# w5500-004.net
KiCad netlist of a schematic drawn in EAGLE
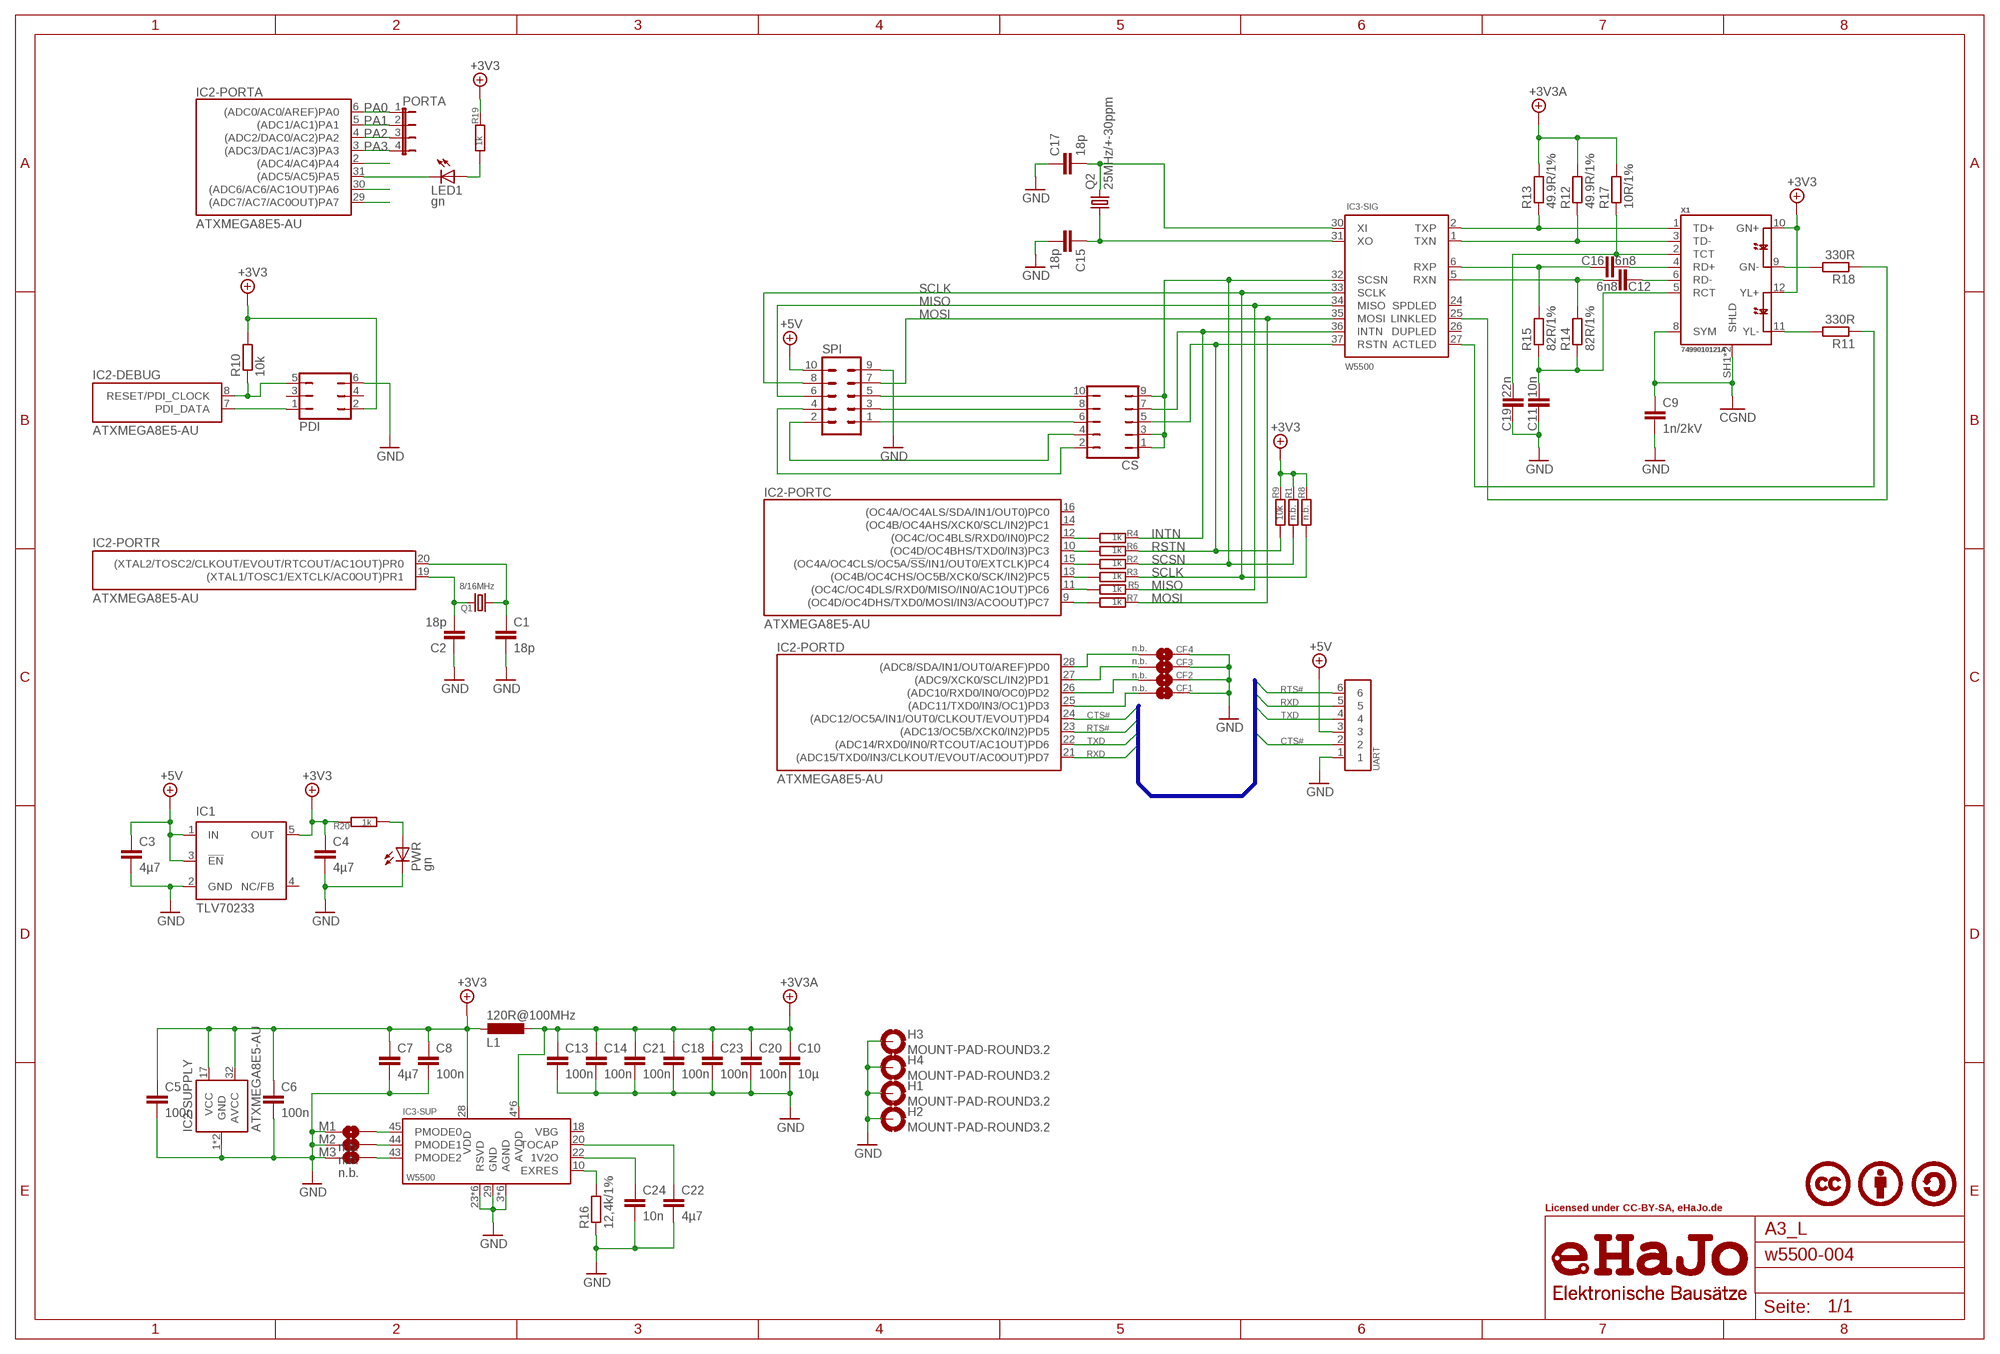
[diagram p0: schematic, sheet 1]

(export (version "E")
  (design (tool "Eeschema 10.0.6"))
  (components
    (comp (ref "C1")
      (value "18p")
      (footprint "eagle-import:C0603")
      (libsource (lib "eagle-import") (part "CC0603"))
    )
    (comp (ref "C2")
      (value "18p")
      (footprint "eagle-import:C0603")
      (libsource (lib "eagle-import") (part "CC0603"))
    )
    (comp (ref "C3")
      (value "4µ7")
      (footprint "eagle-import:C0805")
      (libsource (lib "eagle-import") (part "CC0805"))
    )
    (comp (ref "C4")
      (value "4µ7")
      (footprint "eagle-import:C0805")
      (libsource (lib "eagle-import") (part "CC0805"))
    )
    (comp (ref "C5")
      (value "100n")
      (footprint "eagle-import:C0603")
      (libsource (lib "eagle-import") (part "CC0603"))
    )
    (comp (ref "C6")
      (value "100n")
      (footprint "eagle-import:C0603")
      (libsource (lib "eagle-import") (part "CC0603"))
    )
    (comp (ref "C7")
      (value "4µ7")
      (footprint "eagle-import:C0805")
      (libsource (lib "eagle-import") (part "CC0805"))
    )
    (comp (ref "C8")
      (value "100n")
      (footprint "eagle-import:C0603")
      (libsource (lib "eagle-import") (part "CC0603"))
    )
    (comp (ref "C9")
      (value "1n/2kV")
      (footprint "eagle-import:C0805")
      (libsource (lib "eagle-import") (part "CC0805"))
    )
    (comp (ref "C10")
      (value "10µ")
      (footprint "eagle-import:C1206")
      (libsource (lib "eagle-import") (part "CC1206"))
    )
    (comp (ref "C11")
      (value "10n")
      (footprint "eagle-import:C0603")
      (libsource (lib "eagle-import") (part "CC0603"))
    )
    (comp (ref "C12")
      (value "6n8")
      (footprint "eagle-import:C0603")
      (libsource (lib "eagle-import") (part "CC0603"))
    )
    (comp (ref "C13")
      (value "100n")
      (footprint "eagle-import:C0603")
      (libsource (lib "eagle-import") (part "CC0603"))
    )
    (comp (ref "C14")
      (value "100n")
      (footprint "eagle-import:C0603")
      (libsource (lib "eagle-import") (part "CC0603"))
    )
    (comp (ref "C15")
      (value "18p")
      (footprint "eagle-import:C0603")
      (libsource (lib "eagle-import") (part "CC0603"))
    )
    (comp (ref "C16")
      (value "6n8")
      (footprint "eagle-import:C0603")
      (libsource (lib "eagle-import") (part "CC0603"))
    )
    (comp (ref "C17")
      (value "18p")
      (footprint "eagle-import:C0603")
      (libsource (lib "eagle-import") (part "CC0603"))
    )
    (comp (ref "C18")
      (value "100n")
      (footprint "eagle-import:C0603")
      (libsource (lib "eagle-import") (part "CC0603"))
    )
    (comp (ref "C19")
      (value "22n")
      (footprint "eagle-import:C0603")
      (libsource (lib "eagle-import") (part "CC0603"))
    )
    (comp (ref "C20")
      (value "100n")
      (footprint "eagle-import:C0603")
      (libsource (lib "eagle-import") (part "CC0603"))
    )
    (comp (ref "C21")
      (value "100n")
      (footprint "eagle-import:C0603")
      (libsource (lib "eagle-import") (part "CC0603"))
    )
    (comp (ref "C22")
      (value "4µ7")
      (footprint "eagle-import:C0805")
      (libsource (lib "eagle-import") (part "CC0805"))
    )
    (comp (ref "C23")
      (value "100n")
      (footprint "eagle-import:C0603")
      (libsource (lib "eagle-import") (part "CC0603"))
    )
    (comp (ref "C24")
      (value "10n")
      (footprint "eagle-import:C0603")
      (libsource (lib "eagle-import") (part "CC0603"))
    )
    (comp (ref "CF1")
      (value "n.b.")
      (footprint "eagle-import:SJS")
      (libsource (lib "eagle-import") (part "SJS"))
    )
    (comp (ref "CF2")
      (value "n.b.")
      (footprint "eagle-import:SJS")
      (libsource (lib "eagle-import") (part "SJS"))
    )
    (comp (ref "CF3")
      (value "n.b.")
      (footprint "eagle-import:SJS")
      (libsource (lib "eagle-import") (part "SJS"))
    )
    (comp (ref "CF4")
      (value "n.b.")
      (footprint "eagle-import:SJS")
      (libsource (lib "eagle-import") (part "SJS"))
    )
    (comp (ref "CS")
      (value "JP5Q")
      (footprint "eagle-import:JP5Q")
      (libsource (lib "eagle-import") (part "JP5Q"))
    )
    (comp (ref "H1")
      (value "MOUNT-PAD-ROUND3.2")
      (footprint "eagle-import:3,2-PAD")
      (libsource (lib "eagle-import") (part "MOUNT-PAD-ROUND3.2"))
    )
    (comp (ref "H2")
      (value "MOUNT-PAD-ROUND3.2")
      (footprint "eagle-import:3,2-PAD")
      (libsource (lib "eagle-import") (part "MOUNT-PAD-ROUND3.2"))
    )
    (comp (ref "H3")
      (value "MOUNT-PAD-ROUND3.2")
      (footprint "eagle-import:3,2-PAD")
      (libsource (lib "eagle-import") (part "MOUNT-PAD-ROUND3.2"))
    )
    (comp (ref "H4")
      (value "MOUNT-PAD-ROUND3.2")
      (footprint "eagle-import:3,2-PAD")
      (libsource (lib "eagle-import") (part "MOUNT-PAD-ROUND3.2"))
    )
    (comp (ref "IC1")
      (value "TLV70233")
      (footprint "eagle-import:SOT23-DBV")
      (libsource (lib "eagle-import") (part "TPS77001"))
    )
    (comp (ref "IC2")
      (value "ATXMEGA8E5-AU")
      (footprint "eagle-import:TQFP32-08")
      (libsource (lib "eagle-import") (part "ATXMEGAE5-AU"))
    )
    (comp (ref "IC3")
      (value "W5500")
      (footprint "eagle-import:LQFP48")
      (libsource (lib "eagle-import") (part "W5500"))
    )
    (comp (ref "L1")
      (value "120R@100MHz")
      (footprint "eagle-import:R0805")
      (libsource (lib "eagle-import") (part "L0805"))
    )
    (comp (ref "LED1")
      (value "gn")
      (footprint "eagle-import:CHIP-LED0805")
      (libsource (lib "eagle-import") (part "LEDCHIP-LED0805"))
    )
    (comp (ref "M1")
      (value "n.b.")
      (footprint "eagle-import:SJS")
      (libsource (lib "eagle-import") (part "SJS"))
    )
    (comp (ref "M2")
      (value "n.b.")
      (footprint "eagle-import:SJS")
      (libsource (lib "eagle-import") (part "SJS"))
    )
    (comp (ref "M3")
      (value "n.b.")
      (footprint "eagle-import:SJS")
      (libsource (lib "eagle-import") (part "SJS"))
    )
    (comp (ref "PDI")
      (value "JP3Q")
      (footprint "eagle-import:JP3Q")
      (libsource (lib "eagle-import") (part "JP3Q"))
    )
    (comp (ref "PORTA")
      (value "JP4ESML")
      (footprint "eagle-import:4SML")
      (libsource (lib "eagle-import") (part "JP4ESML"))
    )
    (comp (ref "PWR")
      (value "gn")
      (footprint "eagle-import:CHIP-LED0805")
      (libsource (lib "eagle-import") (part "LEDCHIP-LED0805"))
    )
    (comp (ref "Q1")
      (value "8/16MHz")
      (footprint "eagle-import:HC49U70")
      (libsource (lib "eagle-import") (part "CRYSTALHC49U70"))
    )
    (comp (ref "Q2")
      (value "25MHz/+-30ppm")
      (footprint "eagle-import:HC49U70")
      (libsource (lib "eagle-import") (part "CRYSTALHC49U70"))
    )
    (comp (ref "R1")
      (value "n.b.")
      (footprint "eagle-import:R0603")
      (libsource (lib "eagle-import") (part "RR0603"))
    )
    (comp (ref "R2")
      (value "1k")
      (footprint "eagle-import:R0603")
      (libsource (lib "eagle-import") (part "RR0603"))
    )
    (comp (ref "R3")
      (value "1k")
      (footprint "eagle-import:R0603")
      (libsource (lib "eagle-import") (part "RR0603"))
    )
    (comp (ref "R4")
      (value "1k")
      (footprint "eagle-import:R0603")
      (libsource (lib "eagle-import") (part "RR0603"))
    )
    (comp (ref "R5")
      (value "1k")
      (footprint "eagle-import:R0603")
      (libsource (lib "eagle-import") (part "RR0603"))
    )
    (comp (ref "R6")
      (value "1k")
      (footprint "eagle-import:R0603")
      (libsource (lib "eagle-import") (part "RR0603"))
    )
    (comp (ref "R7")
      (value "1k")
      (footprint "eagle-import:R0603")
      (libsource (lib "eagle-import") (part "RR0603"))
    )
    (comp (ref "R8")
      (value "n.b.")
      (footprint "eagle-import:R0603")
      (libsource (lib "eagle-import") (part "RR0603"))
    )
    (comp (ref "R9")
      (value "10k")
      (footprint "eagle-import:R0603")
      (libsource (lib "eagle-import") (part "RR0603"))
    )
    (comp (ref "R10")
      (value "10k")
      (footprint "eagle-import:R0603")
      (libsource (lib "eagle-import") (part "RR0603"))
    )
    (comp (ref "R11")
      (value "330R")
      (footprint "eagle-import:R0603")
      (libsource (lib "eagle-import") (part "RR0603"))
    )
    (comp (ref "R12")
      (value "49.9R/1%")
      (footprint "eagle-import:R0603")
      (libsource (lib "eagle-import") (part "RR0603"))
    )
    (comp (ref "R13")
      (value "49.9R/1%")
      (footprint "eagle-import:R0603")
      (libsource (lib "eagle-import") (part "RR0603"))
    )
    (comp (ref "R14")
      (value "82R/1%")
      (footprint "eagle-import:R0603")
      (libsource (lib "eagle-import") (part "RR0603"))
    )
    (comp (ref "R15")
      (value "82R/1%")
      (footprint "eagle-import:R0603")
      (libsource (lib "eagle-import") (part "RR0603"))
    )
    (comp (ref "R16")
      (value "12,4k/1%")
      (footprint "eagle-import:R0603")
      (libsource (lib "eagle-import") (part "RR0603"))
    )
    (comp (ref "R17")
      (value "10R/1%")
      (footprint "eagle-import:R0603")
      (libsource (lib "eagle-import") (part "RR0603"))
    )
    (comp (ref "R18")
      (value "330R")
      (footprint "eagle-import:R0603")
      (libsource (lib "eagle-import") (part "RR0603"))
    )
    (comp (ref "R19")
      (value "1k")
      (footprint "eagle-import:R0603")
      (libsource (lib "eagle-import") (part "RR0603"))
    )
    (comp (ref "R20")
      (value "1k")
      (footprint "eagle-import:R0603")
      (libsource (lib "eagle-import") (part "RR0603"))
    )
    (comp (ref "SPI")
      (value "ML10")
      (footprint "eagle-import:ML10")
      (libsource (lib "eagle-import") (part "ML10"))
    )
    (comp (ref "UART")
      (value "JP6E")
      (footprint "eagle-import:JP6E")
      (libsource (lib "eagle-import") (part "JP6E"))
    )
    (comp (ref "X1")
      (value "7499010121A")
      (footprint "eagle-import:121A")
      (libsource (lib "eagle-import") (part "7499010121"))
    )
  )
  (nets
    (net (code "1") (name "+3V3") (class "Default")
      (node (ref "C4") (pin "1") (pinfunction "1_1") (pintype "passive"))
      (node (ref "C5") (pin "1") (pinfunction "1_1") (pintype "passive"))
      (node (ref "C6") (pin "1") (pinfunction "1_1") (pintype "passive"))
      (node (ref "C7") (pin "1") (pinfunction "1_1") (pintype "passive"))
      (node (ref "C8") (pin "1") (pinfunction "1_1") (pintype "passive"))
      (node (ref "IC1") (pin "5") (pinfunction "OUT_5") (pintype "passive"))
      (node (ref "IC2") (pin "17") (pinfunction "VCC_17") (pintype "bidirectional"))
      (node (ref "IC2") (pin "32") (pinfunction "AVCC_32") (pintype "bidirectional"))
      (node (ref "IC3") (pin "28") (pinfunction "VDD_28") (pintype "power_in"))
      (node (ref "L1") (pin "2") (pinfunction "2_2") (pintype "passive"))
      (node (ref "PDI") (pin "2") (pinfunction "2_2") (pintype "passive"))
      (node (ref "R1") (pin "2") (pinfunction "2_2") (pintype "passive"))
      (node (ref "R10") (pin "2") (pinfunction "2_2") (pintype "passive"))
      (node (ref "R19") (pin "2") (pinfunction "2_2") (pintype "passive"))
      (node (ref "R20") (pin "2") (pinfunction "2_2") (pintype "passive"))
      (node (ref "R8") (pin "2") (pinfunction "2_2") (pintype "passive"))
      (node (ref "R9") (pin "2") (pinfunction "2_2") (pintype "passive"))
      (node (ref "X1") (pin "10") (pinfunction "GN+_10") (pintype "bidirectional"))
      (node (ref "X1") (pin "12") (pinfunction "YL+_12") (pintype "bidirectional"))
    )
    (net (code "2") (name "+3V3A") (class "Default")
      (node (ref "C10") (pin "1") (pinfunction "1_1") (pintype "passive"))
      (node (ref "C13") (pin "1") (pinfunction "1_1") (pintype "passive"))
      (node (ref "C14") (pin "1") (pinfunction "1_1") (pintype "passive"))
      (node (ref "C18") (pin "1") (pinfunction "1_1") (pintype "passive"))
      (node (ref "C20") (pin "1") (pinfunction "1_1") (pintype "passive"))
      (node (ref "C21") (pin "1") (pinfunction "1_1") (pintype "passive"))
      (node (ref "C23") (pin "1") (pinfunction "1_1") (pintype "passive"))
      (node (ref "IC3") (pin "11") (pinfunction "AVDD_11") (pintype "power_in"))
      (node (ref "IC3") (pin "15") (pinfunction "AVDD_15") (pintype "power_in"))
      (node (ref "IC3") (pin "17") (pinfunction "AVDD_17") (pintype "power_in"))
      (node (ref "IC3") (pin "21") (pinfunction "AVDD_21") (pintype "power_in"))
      (node (ref "IC3") (pin "4") (pinfunction "AVDD_4") (pintype "power_in"))
      (node (ref "IC3") (pin "8") (pinfunction "AVDD_8") (pintype "power_in"))
      (node (ref "L1") (pin "1") (pinfunction "1_1") (pintype "passive"))
      (node (ref "R12") (pin "2") (pinfunction "2_2") (pintype "passive"))
      (node (ref "R13") (pin "2") (pinfunction "2_2") (pintype "passive"))
      (node (ref "R17") (pin "2") (pinfunction "2_2") (pintype "passive"))
    )
    (net (code "3") (name "+5V") (class "Default")
      (node (ref "C3") (pin "1") (pinfunction "1_1") (pintype "passive"))
      (node (ref "IC1") (pin "1") (pinfunction "IN_1") (pintype "input"))
      (node (ref "IC1") (pin "3") (pinfunction "~{EN}_3") (pintype "input"))
      (node (ref "SPI") (pin "10") (pinfunction "10_10") (pintype "passive"))
      (node (ref "UART") (pin "3") (pinfunction "3_3") (pintype "bidirectional"))
    )
    (net (code "4") (name "/CTS#") (class "Default")
      (node (ref "IC2") (pin "24") (pinfunction "(ADC12/OC5A/IN1/OUT0/CLKOUT/EVOUT)PD4_24") (pintype "bidirectional"))
      (node (ref "UART") (pin "2") (pinfunction "2_2") (pintype "bidirectional"))
    )
    (net (code "5") (name "/INTN") (class "Default")
      (node (ref "CS") (pin "7") (pinfunction "7_7") (pintype "passive"))
      (node (ref "IC3") (pin "36") (pinfunction "INTN_36") (pintype "output"))
      (node (ref "R4") (pin "1") (pinfunction "1_1") (pintype "passive"))
    )
    (net (code "6") (name "/MISO") (class "Default")
      (node (ref "IC3") (pin "34") (pinfunction "MISO_34") (pintype "output"))
      (node (ref "R5") (pin "1") (pinfunction "1_1") (pintype "passive"))
      (node (ref "SPI") (pin "6") (pinfunction "6_6") (pintype "passive"))
    )
    (net (code "7") (name "/MOSI") (class "Default")
      (node (ref "IC3") (pin "35") (pinfunction "MOSI_35") (pintype "input"))
      (node (ref "R7") (pin "1") (pinfunction "1_1") (pintype "passive"))
      (node (ref "SPI") (pin "7") (pinfunction "7_7") (pintype "passive"))
    )
    (net (code "8") (name "/PA0") (class "Default")
      (node (ref "IC2") (pin "6") (pinfunction "(ADC0/AC0/AREF)PA0_6") (pintype "bidirectional"))
      (node (ref "PORTA") (pin "1") (pinfunction "1_1") (pintype "passive"))
    )
    (net (code "9") (name "/PA1") (class "Default")
      (node (ref "IC2") (pin "5") (pinfunction "(ADC1/AC1)PA1_5") (pintype "bidirectional"))
      (node (ref "PORTA") (pin "2") (pinfunction "2_2") (pintype "passive"))
    )
    (net (code "10") (name "/PA2") (class "Default")
      (node (ref "IC2") (pin "4") (pinfunction "(ADC2/DAC0/AC2)PA2_4") (pintype "bidirectional"))
      (node (ref "PORTA") (pin "3") (pinfunction "3_3") (pintype "passive"))
    )
    (net (code "11") (name "/PA3") (class "Default")
      (node (ref "IC2") (pin "3") (pinfunction "(ADC3/DAC1/AC3)PA3_3") (pintype "bidirectional"))
      (node (ref "PORTA") (pin "4") (pinfunction "4_4") (pintype "passive"))
    )
    (net (code "12") (name "/RSTN") (class "Default")
      (node (ref "CS") (pin "5") (pinfunction "5_5") (pintype "passive"))
      (node (ref "IC3") (pin "37") (pinfunction "RSTN_37") (pintype "input"))
      (node (ref "R6") (pin "1") (pinfunction "1_1") (pintype "passive"))
      (node (ref "R9") (pin "1") (pinfunction "1_1") (pintype "passive"))
    )
    (net (code "13") (name "/RTS#") (class "Default")
      (node (ref "IC2") (pin "23") (pinfunction "(ADC13/OC5B/XCK0/IN2)PD5_23") (pintype "bidirectional"))
      (node (ref "UART") (pin "6") (pinfunction "6_6") (pintype "bidirectional"))
    )
    (net (code "14") (name "/RXD") (class "Default")
      (node (ref "IC2") (pin "21") (pinfunction "(ADC15/TXD0/IN3/CLKOUT/EVOUT/AC0OUT)PD7_21") (pintype "bidirectional"))
      (node (ref "UART") (pin "5") (pinfunction "5_5") (pintype "bidirectional"))
    )
    (net (code "15") (name "/SCLK") (class "Default")
      (node (ref "IC3") (pin "33") (pinfunction "SCLK_33") (pintype "input"))
      (node (ref "R3") (pin "1") (pinfunction "1_1") (pintype "passive"))
      (node (ref "R8") (pin "1") (pinfunction "1_1") (pintype "passive"))
      (node (ref "SPI") (pin "8") (pinfunction "8_8") (pintype "passive"))
    )
    (net (code "16") (name "/SCSN") (class "Default")
      (node (ref "CS") (pin "1") (pinfunction "1_1") (pintype "passive"))
      (node (ref "CS") (pin "3") (pinfunction "3_3") (pintype "passive"))
      (node (ref "CS") (pin "9") (pinfunction "9_9") (pintype "passive"))
      (node (ref "IC3") (pin "32") (pinfunction "SCSN_32") (pintype "input"))
      (node (ref "R1") (pin "1") (pinfunction "1_1") (pintype "passive"))
      (node (ref "R2") (pin "1") (pinfunction "1_1") (pintype "passive"))
    )
    (net (code "17") (name "/TXD") (class "Default")
      (node (ref "IC2") (pin "22") (pinfunction "(ADC14/RXD0/IN0/RTCOUT/AC1OUT)PD6_22") (pintype "bidirectional"))
      (node (ref "UART") (pin "4") (pinfunction "4_4") (pintype "bidirectional"))
    )
    (net (code "18") (name "CGND") (class "Default")
      (node (ref "C9") (pin "1") (pinfunction "1_1") (pintype "passive"))
      (node (ref "X1") (pin "8") (pinfunction "SYM_8") (pintype "bidirectional"))
      (node (ref "X1") (pin "SH1") (pinfunction "SHLD_SH1") (pintype "bidirectional"))
      (node (ref "X1") (pin "SH2") (pinfunction "SHLD_SH2") (pintype "bidirectional"))
    )
    (net (code "19") (name "GND") (class "Default")
      (node (ref "C1") (pin "2") (pinfunction "2_2") (pintype "passive"))
      (node (ref "C10") (pin "2") (pinfunction "2_2") (pintype "passive"))
      (node (ref "C11") (pin "1") (pinfunction "1_1") (pintype "passive"))
      (node (ref "C13") (pin "2") (pinfunction "2_2") (pintype "passive"))
      (node (ref "C14") (pin "2") (pinfunction "2_2") (pintype "passive"))
      (node (ref "C15") (pin "2") (pinfunction "2_2") (pintype "passive"))
      (node (ref "C17") (pin "1") (pinfunction "1_1") (pintype "passive"))
      (node (ref "C18") (pin "2") (pinfunction "2_2") (pintype "passive"))
      (node (ref "C19") (pin "1") (pinfunction "1_1") (pintype "passive"))
      (node (ref "C2") (pin "1") (pinfunction "1_1") (pintype "passive"))
      (node (ref "C20") (pin "2") (pinfunction "2_2") (pintype "passive"))
      (node (ref "C21") (pin "2") (pinfunction "2_2") (pintype "passive"))
      (node (ref "C22") (pin "2") (pinfunction "2_2") (pintype "passive"))
      (node (ref "C23") (pin "2") (pinfunction "2_2") (pintype "passive"))
      (node (ref "C24") (pin "2") (pinfunction "2_2") (pintype "passive"))
      (node (ref "C3") (pin "2") (pinfunction "2_2") (pintype "passive"))
      (node (ref "C4") (pin "2") (pinfunction "2_2") (pintype "passive"))
      (node (ref "C5") (pin "2") (pinfunction "2_2") (pintype "passive"))
      (node (ref "C6") (pin "2") (pinfunction "2_2") (pintype "passive"))
      (node (ref "C7") (pin "2") (pinfunction "2_2") (pintype "passive"))
      (node (ref "C8") (pin "2") (pinfunction "2_2") (pintype "passive"))
      (node (ref "C9") (pin "2") (pinfunction "2_2") (pintype "passive"))
      (node (ref "CF1") (pin "2") (pinfunction "2_2") (pintype "passive"))
      (node (ref "CF2") (pin "2") (pinfunction "2_2") (pintype "passive"))
      (node (ref "CF3") (pin "2") (pinfunction "2_2") (pintype "passive"))
      (node (ref "CF4") (pin "2") (pinfunction "2_2") (pintype "passive"))
      (node (ref "H1") (pin "B3,2") (pinfunction "MOUNT_B3,2") (pintype "passive"))
      (node (ref "H2") (pin "B3,2") (pinfunction "MOUNT_B3,2") (pintype "passive"))
      (node (ref "H3") (pin "B3,2") (pinfunction "MOUNT_B3,2") (pintype "passive"))
      (node (ref "H4") (pin "B3,2") (pinfunction "MOUNT_B3,2") (pintype "passive"))
      (node (ref "IC1") (pin "2") (pinfunction "GND_2") (pintype "power_in"))
      (node (ref "IC2") (pin "1") (pinfunction "GND_1") (pintype "bidirectional"))
      (node (ref "IC2") (pin "18") (pinfunction "GND_18") (pintype "bidirectional"))
      (node (ref "IC3") (pin "14") (pinfunction "AGND_14") (pintype "power_in"))
      (node (ref "IC3") (pin "16") (pinfunction "AGND_16") (pintype "power_in"))
      (node (ref "IC3") (pin "19") (pinfunction "AGND_19") (pintype "power_in"))
      (node (ref "IC3") (pin "23") (pinfunction "RSVD_23") (pintype "input"))
      (node (ref "IC3") (pin "29") (pinfunction "GND_29") (pintype "power_in"))
      (node (ref "IC3") (pin "3") (pinfunction "AGND_3") (pintype "power_in"))
      (node (ref "IC3") (pin "38") (pinfunction "RSVD_38") (pintype "input"))
      (node (ref "IC3") (pin "39") (pinfunction "RSVD_39") (pintype "input"))
      (node (ref "IC3") (pin "40") (pinfunction "RSVD_40") (pintype "input"))
      (node (ref "IC3") (pin "41") (pinfunction "RSVD_41") (pintype "input"))
      (node (ref "IC3") (pin "42") (pinfunction "RSVD_42") (pintype "input"))
      (node (ref "IC3") (pin "48") (pinfunction "AGND_48") (pintype "power_in"))
      (node (ref "IC3") (pin "9") (pinfunction "AGND_9") (pintype "power_in"))
      (node (ref "M1") (pin "1") (pinfunction "1_1") (pintype "passive"))
      (node (ref "M2") (pin "1") (pinfunction "1_1") (pintype "passive"))
      (node (ref "M3") (pin "1") (pinfunction "1_1") (pintype "passive"))
      (node (ref "PDI") (pin "6") (pinfunction "6_6") (pintype "passive"))
      (node (ref "PWR") (pin "C") (pinfunction "C_C") (pintype "passive"))
      (node (ref "R16") (pin "1") (pinfunction "1_1") (pintype "passive"))
      (node (ref "SPI") (pin "9") (pinfunction "9_9") (pintype "passive"))
      (node (ref "UART") (pin "1") (pinfunction "1_1") (pintype "bidirectional"))
    )
    (net (code "20") (name "Net-(CS-Pad2)") (class "Default")
      (node (ref "CS") (pin "2") (pinfunction "2_2") (pintype "passive"))
      (node (ref "SPI") (pin "4") (pinfunction "4_4") (pintype "passive"))
    )
    (net (code "21") (name "Net-(CS-Pad4)") (class "Default")
      (node (ref "CS") (pin "4") (pinfunction "4_4") (pintype "passive"))
      (node (ref "SPI") (pin "2") (pinfunction "2_2") (pintype "passive"))
    )
    (net (code "22") (name "Net-(CS-Pad6)") (class "Default")
      (node (ref "CS") (pin "6") (pinfunction "6_6") (pintype "passive"))
      (node (ref "SPI") (pin "1") (pinfunction "1_1") (pintype "passive"))
    )
    (net (code "23") (name "Net-(CS-Pad8)") (class "Default")
      (node (ref "CS") (pin "8") (pinfunction "8_8") (pintype "passive"))
      (node (ref "SPI") (pin "3") (pinfunction "3_3") (pintype "passive"))
    )
    (net (code "24") (name "Net-(CS-Pad10)") (class "Default")
      (node (ref "CS") (pin "10") (pinfunction "10_10") (pintype "passive"))
      (node (ref "SPI") (pin "5") (pinfunction "5_5") (pintype "passive"))
    )
    (net (code "25") (name "Net-(IC2A-PDI_DATA)") (class "Default")
      (node (ref "IC2") (pin "7") (pinfunction "PDI_DATA_7") (pintype "bidirectional"))
      (node (ref "PDI") (pin "1") (pinfunction "1_1") (pintype "passive"))
    )
    (net (code "26") (name "Net-(IC2A-RESET{slash}PDI_CLOCK)") (class "Default")
      (node (ref "IC2") (pin "8") (pinfunction "RESET/PDI_CLOCK_8") (pintype "bidirectional"))
      (node (ref "PDI") (pin "5") (pinfunction "5_5") (pintype "passive"))
      (node (ref "R10") (pin "1") (pinfunction "1_1") (pintype "passive"))
    )
    (net (code "27") (name "Net-(IC2B-(ADC5{slash}AC5)PA5)") (class "Default")
      (node (ref "IC2") (pin "31") (pinfunction "(ADC5/AC5)PA5_31") (pintype "bidirectional"))
      (node (ref "LED1") (pin "C") (pinfunction "C_C") (pintype "passive"))
    )
    (net (code "28") (name "Net-(IC2C-(OC4A{slash}OC4CLS{slash}OC5A{slash}~{SS}{slash}IN1{slash}OUT0{slash}EXTCLK)PC4)") (class "Default")
      (node (ref "IC2") (pin "15") (pinfunction "(OC4A/OC4CLS/OC5A/~{SS}/IN1/OUT0/EXTCLK)PC4_15") (pintype "bidirectional"))
      (node (ref "R2") (pin "2") (pinfunction "2_2") (pintype "passive"))
    )
    (net (code "29") (name "Net-(IC2C-(OC4B{slash}OC4CHS{slash}OC5B{slash}XCK0{slash}SCK{slash}IN2)PC5)") (class "Default")
      (node (ref "IC2") (pin "13") (pinfunction "(OC4B/OC4CHS/OC5B/XCK0/SCK/IN2)PC5_13") (pintype "bidirectional"))
      (node (ref "R3") (pin "2") (pinfunction "2_2") (pintype "passive"))
    )
    (net (code "30") (name "Net-(IC2C-(OC4C{slash}OC4BLS{slash}RXD0{slash}IN0)PC2)") (class "Default")
      (node (ref "IC2") (pin "12") (pinfunction "(OC4C/OC4BLS/RXD0/IN0)PC2_12") (pintype "bidirectional"))
      (node (ref "R4") (pin "2") (pinfunction "2_2") (pintype "passive"))
    )
    (net (code "31") (name "Net-(IC2C-(OC4C{slash}OC4DLS{slash}RXD0{slash}MISO{slash}IN0{slash}AC1OUT)PC6)") (class "Default")
      (node (ref "IC2") (pin "11") (pinfunction "(OC4C/OC4DLS/RXD0/MISO/IN0/AC1OUT)PC6_11") (pintype "bidirectional"))
      (node (ref "R5") (pin "2") (pinfunction "2_2") (pintype "passive"))
    )
    (net (code "32") (name "Net-(IC2C-(OC4D{slash}OC4BHS{slash}TXD0{slash}IN3)PC3)") (class "Default")
      (node (ref "IC2") (pin "10") (pinfunction "(OC4D/OC4BHS/TXD0/IN3)PC3_10") (pintype "bidirectional"))
      (node (ref "R6") (pin "2") (pinfunction "2_2") (pintype "passive"))
    )
    (net (code "33") (name "Net-(IC2C-(OC4D{slash}OC4DHS{slash}TXD0{slash}MOSI{slash}IN3{slash}ACOOUT)PC7)") (class "Default")
      (node (ref "IC2") (pin "9") (pinfunction "(OC4D/OC4DHS/TXD0/MOSI/IN3/ACOOUT)PC7_9") (pintype "bidirectional"))
      (node (ref "R7") (pin "2") (pinfunction "2_2") (pintype "passive"))
    )
    (net (code "34") (name "Net-(IC2D-(ADC8{slash}SDA{slash}IN1{slash}OUT0{slash}AREF)PD0)") (class "Default")
      (node (ref "CF4") (pin "1") (pinfunction "1_1") (pintype "passive"))
      (node (ref "IC2") (pin "28") (pinfunction "(ADC8/SDA/IN1/OUT0/AREF)PD0_28") (pintype "bidirectional"))
    )
    (net (code "35") (name "Net-(IC2D-(ADC9{slash}XCK0{slash}SCL{slash}IN2)PD1)") (class "Default")
      (node (ref "CF3") (pin "1") (pinfunction "1_1") (pintype "passive"))
      (node (ref "IC2") (pin "27") (pinfunction "(ADC9/XCK0/SCL/IN2)PD1_27") (pintype "bidirectional"))
    )
    (net (code "36") (name "Net-(IC2D-(ADC10{slash}RXD0{slash}IN0{slash}OC0)PD2)") (class "Default")
      (node (ref "CF2") (pin "1") (pinfunction "1_1") (pintype "passive"))
      (node (ref "IC2") (pin "26") (pinfunction "(ADC10/RXD0/IN0/OC0)PD2_26") (pintype "bidirectional"))
    )
    (net (code "37") (name "Net-(IC2D-(ADC11{slash}TXD0{slash}IN3{slash}OC1)PD3)") (class "Default")
      (node (ref "CF1") (pin "1") (pinfunction "1_1") (pintype "passive"))
      (node (ref "IC2") (pin "25") (pinfunction "(ADC11/TXD0/IN3/OC1)PD3_25") (pintype "bidirectional"))
    )
    (net (code "38") (name "Net-(IC2E-(XTAL1{slash}TOSC1{slash}EXTCLK{slash}AC0OUT)PR1)") (class "Default")
      (node (ref "C2") (pin "2") (pinfunction "2_2") (pintype "passive"))
      (node (ref "IC2") (pin "19") (pinfunction "(XTAL1/TOSC1/EXTCLK/AC0OUT)PR1_19") (pintype "bidirectional"))
      (node (ref "Q1") (pin "1") (pinfunction "1_1") (pintype "passive"))
    )
    (net (code "39") (name "Net-(IC2E-(XTAL2{slash}TOSC2{slash}CLKOUT{slash}EVOUT{slash}RTCOUT{slash}AC1OUT)PR0)") (class "Default")
      (node (ref "C1") (pin "1") (pinfunction "1_1") (pintype "passive"))
      (node (ref "IC2") (pin "20") (pinfunction "(XTAL2/TOSC2/CLKOUT/EVOUT/RTCOUT/AC1OUT)PR0_20") (pintype "bidirectional"))
      (node (ref "Q1") (pin "2") (pinfunction "2_2") (pintype "passive"))
    )
    (net (code "40") (name "Net-(IC3A-ACTLED)") (class "Default")
      (node (ref "IC3") (pin "27") (pinfunction "ACTLED_27") (pintype "output"))
      (node (ref "R11") (pin "1") (pinfunction "1_1") (pintype "passive"))
    )
    (net (code "41") (name "Net-(IC3A-LINKLED)") (class "Default")
      (node (ref "IC3") (pin "25") (pinfunction "LINKLED_25") (pintype "output"))
      (node (ref "R18") (pin "1") (pinfunction "1_1") (pintype "passive"))
    )
    (net (code "42") (name "Net-(IC3A-RXN)") (class "Default")
      (node (ref "C12") (pin "2") (pinfunction "2_2") (pintype "passive"))
      (node (ref "IC3") (pin "5") (pinfunction "RXN_5") (pintype "input"))
      (node (ref "R14") (pin "2") (pinfunction "2_2") (pintype "passive"))
    )
    (net (code "43") (name "Net-(IC3A-RXP)") (class "Default")
      (node (ref "C16") (pin "1") (pinfunction "1_1") (pintype "passive"))
      (node (ref "IC3") (pin "6") (pinfunction "RXP_6") (pintype "input"))
      (node (ref "R15") (pin "2") (pinfunction "2_2") (pintype "passive"))
    )
    (net (code "44") (name "Net-(IC3A-TXN)") (class "Default")
      (node (ref "IC3") (pin "1") (pinfunction "TXN_1") (pintype "output"))
      (node (ref "R12") (pin "1") (pinfunction "1_1") (pintype "passive"))
      (node (ref "X1") (pin "3") (pinfunction "TD-_3") (pintype "bidirectional"))
    )
    (net (code "45") (name "Net-(IC3A-TXP)") (class "Default")
      (node (ref "IC3") (pin "2") (pinfunction "TXP_2") (pintype "output"))
      (node (ref "R13") (pin "1") (pinfunction "1_1") (pintype "passive"))
      (node (ref "X1") (pin "1") (pinfunction "TD+_1") (pintype "bidirectional"))
    )
    (net (code "46") (name "Net-(IC3A-XI)") (class "Default")
      (node (ref "C17") (pin "2") (pinfunction "2_2") (pintype "passive"))
      (node (ref "IC3") (pin "30") (pinfunction "XI_30") (pintype "input"))
      (node (ref "Q2") (pin "2") (pinfunction "2_2") (pintype "passive"))
    )
    (net (code "47") (name "Net-(IC3A-XO)") (class "Default")
      (node (ref "C15") (pin "1") (pinfunction "1_1") (pintype "passive"))
      (node (ref "IC3") (pin "31") (pinfunction "XO_31") (pintype "output"))
      (node (ref "Q2") (pin "1") (pinfunction "1_1") (pintype "passive"))
    )
    (net (code "48") (name "Net-(IC3B-1V2O)") (class "Default")
      (node (ref "C24") (pin "1") (pinfunction "1_1") (pintype "passive"))
      (node (ref "IC3") (pin "22") (pinfunction "1V2O_22") (pintype "output"))
    )
    (net (code "49") (name "Net-(IC3B-EXRES)") (class "Default")
      (node (ref "IC3") (pin "10") (pinfunction "EXRES_10") (pintype "bidirectional"))
      (node (ref "R16") (pin "2") (pinfunction "2_2") (pintype "passive"))
    )
    (net (code "50") (name "Net-(IC3B-PMODE0)") (class "Default")
      (node (ref "IC3") (pin "45") (pinfunction "PMODE0_45") (pintype "input"))
      (node (ref "M1") (pin "2") (pinfunction "2_2") (pintype "passive"))
    )
    (net (code "51") (name "Net-(IC3B-PMODE1)") (class "Default")
      (node (ref "IC3") (pin "44") (pinfunction "PMODE1_44") (pintype "input"))
      (node (ref "M2") (pin "2") (pinfunction "2_2") (pintype "passive"))
    )
    (net (code "52") (name "Net-(IC3B-PMODE2)") (class "Default")
      (node (ref "IC3") (pin "43") (pinfunction "PMODE2_43") (pintype "input"))
      (node (ref "M3") (pin "2") (pinfunction "2_2") (pintype "passive"))
    )
    (net (code "53") (name "Net-(IC3B-TOCAP)") (class "Default")
      (node (ref "C22") (pin "1") (pinfunction "1_1") (pintype "passive"))
      (node (ref "IC3") (pin "20") (pinfunction "TOCAP_20") (pintype "output"))
    )
    (net (code "54") (name "Net-(LED1-PadA)") (class "Default")
      (node (ref "LED1") (pin "A") (pinfunction "A_A") (pintype "passive"))
      (node (ref "R19") (pin "1") (pinfunction "1_1") (pintype "passive"))
    )
    (net (code "55") (name "Net-(PWR-PadA)") (class "Default")
      (node (ref "PWR") (pin "A") (pinfunction "A_A") (pintype "passive"))
      (node (ref "R20") (pin "1") (pinfunction "1_1") (pintype "passive"))
    )
    (net (code "56") (name "Net-(X1-GN-)") (class "Default")
      (node (ref "R18") (pin "2") (pinfunction "2_2") (pintype "passive"))
      (node (ref "X1") (pin "9") (pinfunction "GN-_9") (pintype "bidirectional"))
    )
    (net (code "57") (name "Net-(X1-RCT)") (class "Default")
      (node (ref "C11") (pin "2") (pinfunction "2_2") (pintype "passive"))
      (node (ref "R14") (pin "1") (pinfunction "1_1") (pintype "passive"))
      (node (ref "R15") (pin "1") (pinfunction "1_1") (pintype "passive"))
      (node (ref "X1") (pin "5") (pinfunction "RCT_5") (pintype "bidirectional"))
    )
    (net (code "58") (name "Net-(X1-RD+)") (class "Default")
      (node (ref "C16") (pin "2") (pinfunction "2_2") (pintype "passive"))
      (node (ref "X1") (pin "4") (pinfunction "RD+_4") (pintype "bidirectional"))
    )
    (net (code "59") (name "Net-(X1-RD-)") (class "Default")
      (node (ref "C12") (pin "1") (pinfunction "1_1") (pintype "passive"))
      (node (ref "X1") (pin "6") (pinfunction "RD-_6") (pintype "bidirectional"))
    )
    (net (code "60") (name "Net-(X1-TCT)") (class "Default")
      (node (ref "C19") (pin "2") (pinfunction "2_2") (pintype "passive"))
      (node (ref "R17") (pin "1") (pinfunction "1_1") (pintype "passive"))
      (node (ref "X1") (pin "2") (pinfunction "TCT_2") (pintype "bidirectional"))
    )
    (net (code "61") (name "Net-(X1-YL-)") (class "Default")
      (node (ref "R11") (pin "2") (pinfunction "2_2") (pintype "passive"))
      (node (ref "X1") (pin "11") (pinfunction "YL-_11") (pintype "bidirectional"))
    )
    (net (code "62") (name "unconnected-(IC1-NC{slash}FB-Pad4)") (class "Default")
      (node (ref "IC1") (pin "4") (pinfunction "NC/FB_4") (pintype "passive"))
    )
    (net (code "63") (name "unconnected-(IC2B-(ADC4{slash}AC4)PA4-Pad2)") (class "Default")
      (node (ref "IC2") (pin "2") (pinfunction "(ADC4/AC4)PA4_2") (pintype "bidirectional"))
    )
    (net (code "64") (name "unconnected-(IC2B-(ADC6{slash}AC6{slash}AC1OUT)PA6-Pad30)") (class "Default")
      (node (ref "IC2") (pin "30") (pinfunction "(ADC6/AC6/AC1OUT)PA6_30") (pintype "bidirectional"))
    )
    (net (code "65") (name "unconnected-(IC2B-(ADC7{slash}AC7{slash}AC0OUT)PA7-Pad29)") (class "Default")
      (node (ref "IC2") (pin "29") (pinfunction "(ADC7/AC7/AC0OUT)PA7_29") (pintype "bidirectional"))
    )
    (net (code "66") (name "unconnected-(IC2C-(OC4A{slash}OC4ALS{slash}SDA{slash}IN1{slash}OUT0)PC0-Pad16)") (class "Default")
      (node (ref "IC2") (pin "16") (pinfunction "(OC4A/OC4ALS/SDA/IN1/OUT0)PC0_16") (pintype "bidirectional"))
    )
    (net (code "67") (name "unconnected-(IC2C-(OC4B{slash}OC4AHS{slash}XCK0{slash}SCL{slash}IN2)PC1-Pad14)") (class "Default")
      (node (ref "IC2") (pin "14") (pinfunction "(OC4B/OC4AHS/XCK0/SCL/IN2)PC1_14") (pintype "bidirectional"))
    )
    (net (code "68") (name "unconnected-(IC3A-DUPLED-Pad26)") (class "Default")
      (node (ref "IC3") (pin "26") (pinfunction "DUPLED_26") (pintype "output"))
    )
    (net (code "69") (name "unconnected-(IC3A-SPDLED-Pad24)") (class "Default")
      (node (ref "IC3") (pin "24") (pinfunction "SPDLED_24") (pintype "output"))
    )
    (net (code "70") (name "unconnected-(IC3B-VBG-Pad18)") (class "Default")
      (node (ref "IC3") (pin "18") (pinfunction "VBG_18") (pintype "output"))
    )
    (net (code "71") (name "unconnected-(PDI-Pad3)") (class "Default")
      (node (ref "PDI") (pin "3") (pinfunction "3_3") (pintype "passive"))
    )
    (net (code "72") (name "unconnected-(PDI-Pad4)") (class "Default")
      (node (ref "PDI") (pin "4") (pinfunction "4_4") (pintype "passive"))
    )
  )
)
